# 1-Schematic_rdb_ruler.net
KiCad netlist of a schematic drawn in EasyEDA
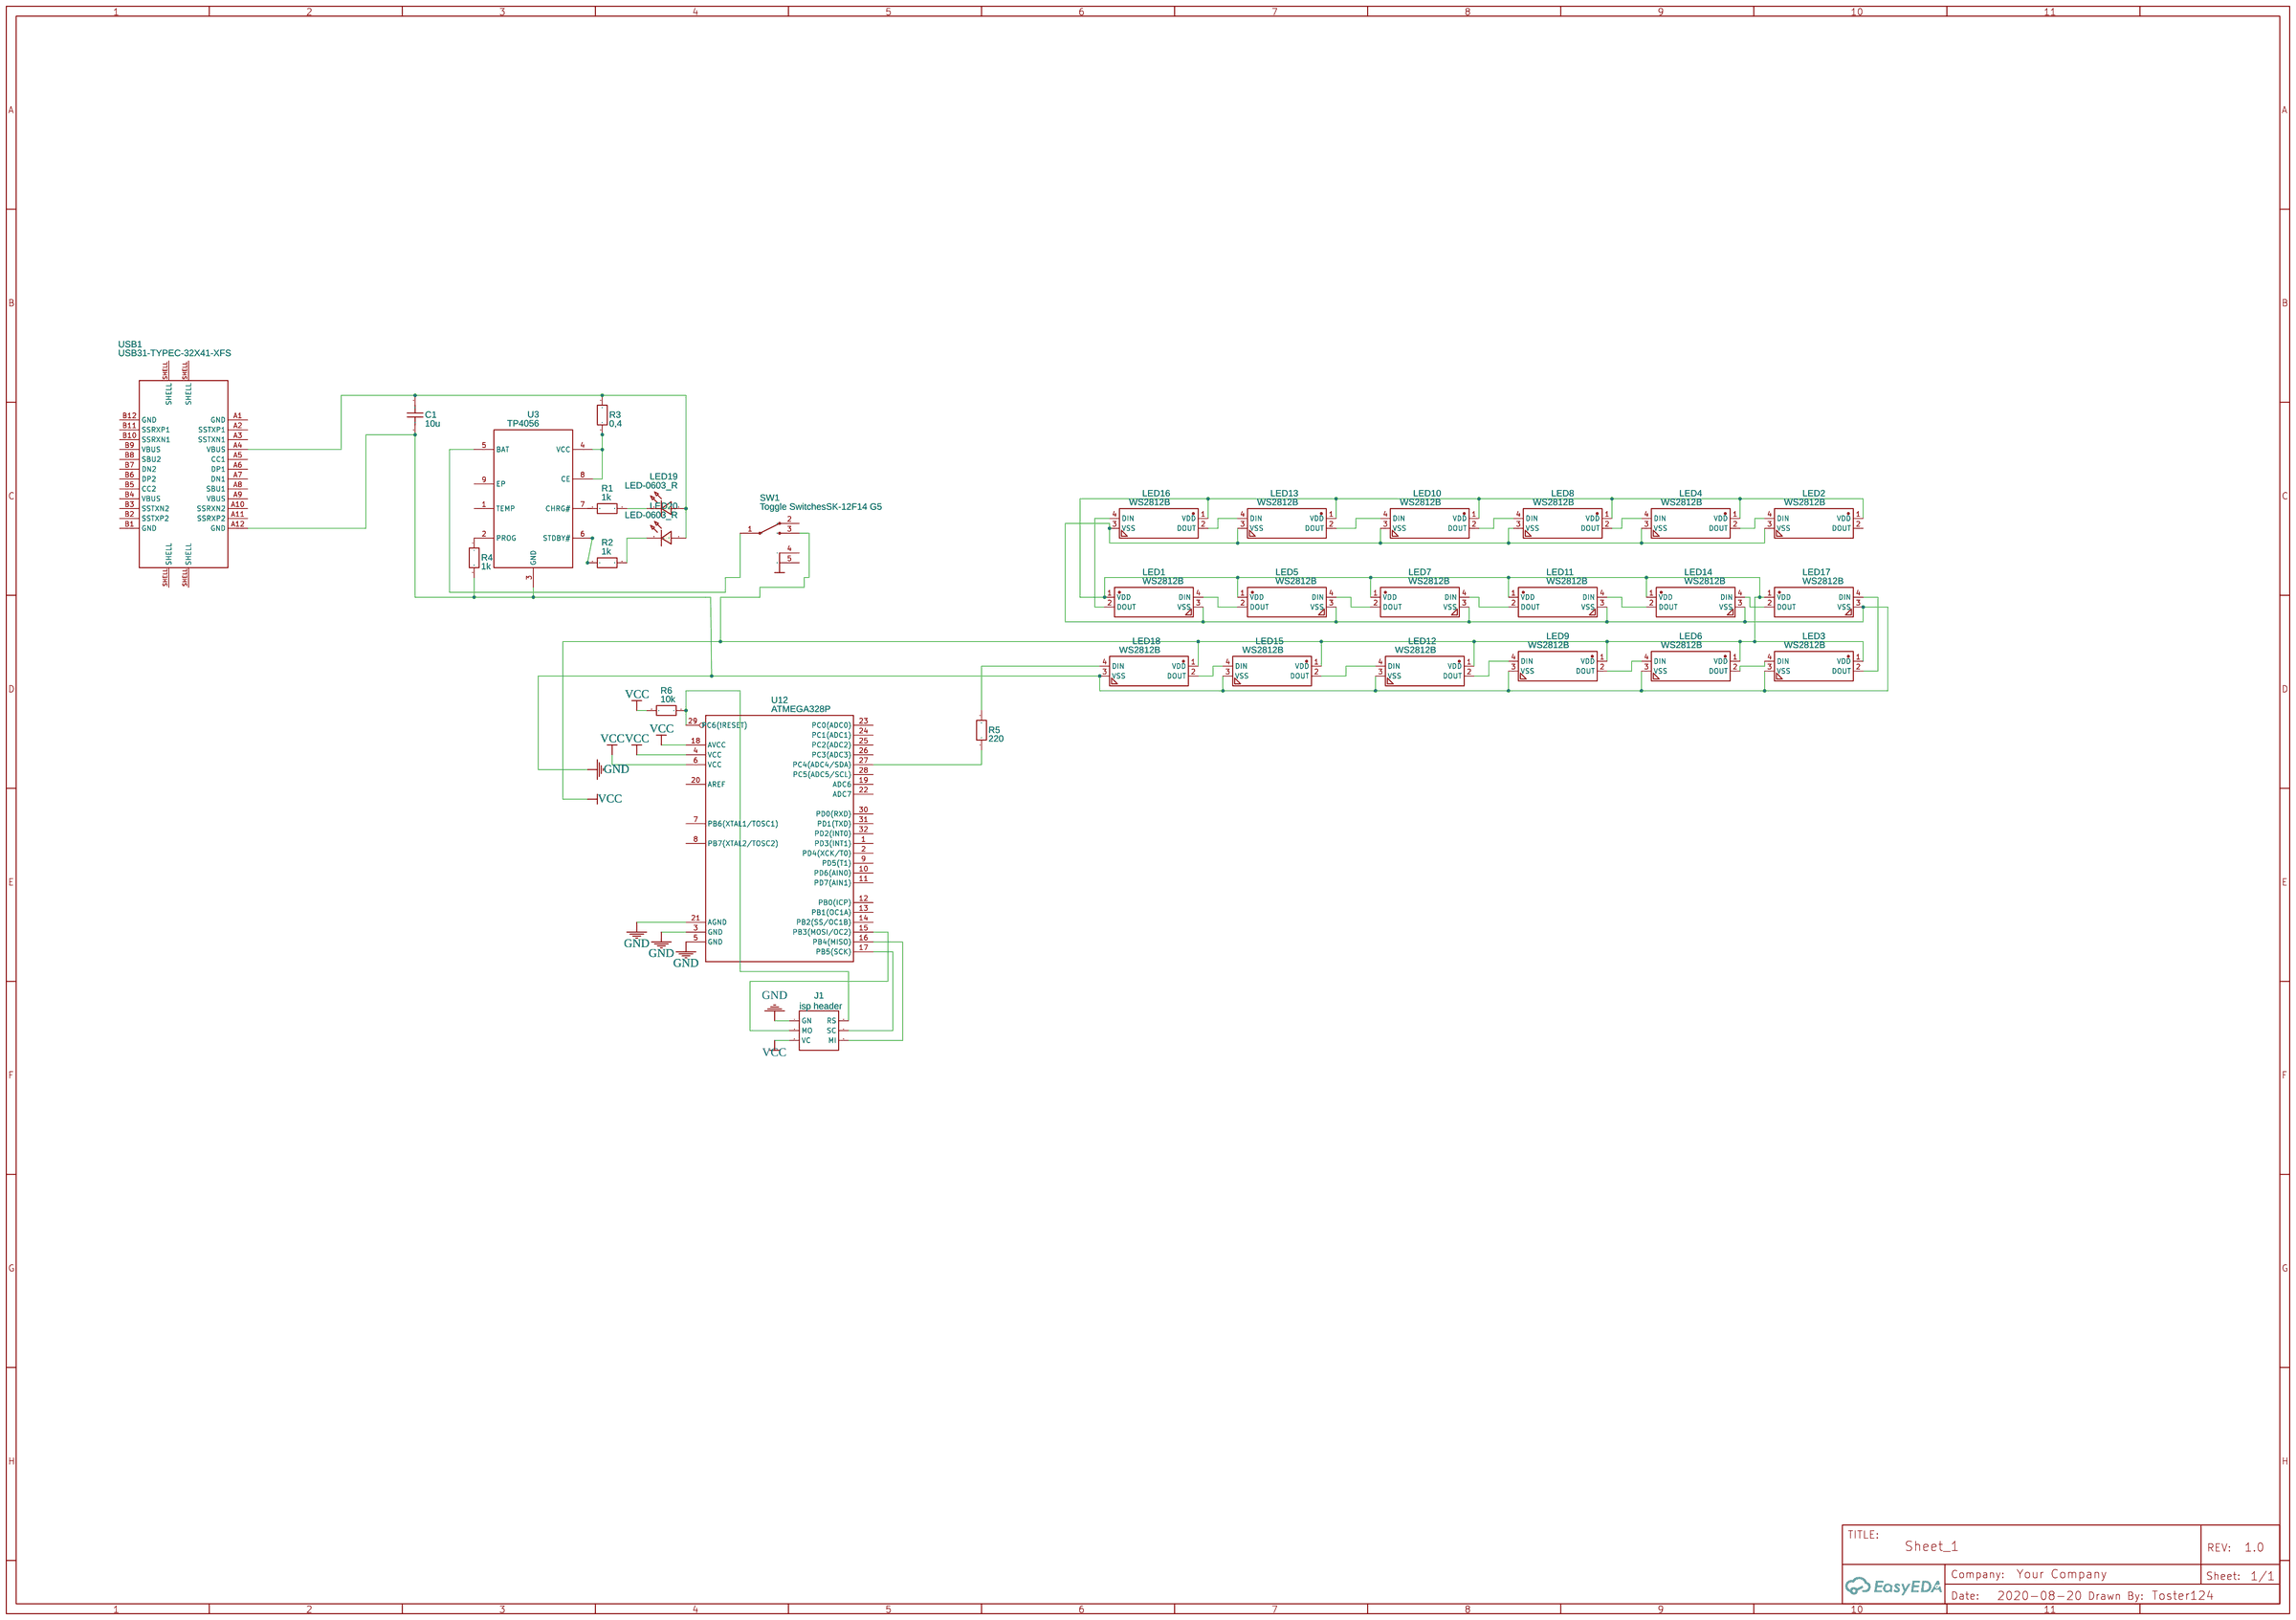
[diagram p0: schematic sheet]

(export (version "E")
  (design (tool "Eeschema 10.0.6"))
  (components
    (comp (ref "C1") (value "10u") (libsource (lib "") (part "C_0603_US")))
    (comp (ref "J1")
      (value "isp header")
      (fields
        (field (name "BOM_Manufacturer Part") "Header-Male-2.54_2x3")
        (field (name "BOM_Supplier Part") "C65114")
      )
      (libsource (lib "") (part "Unknown_1215_-905"))
    )
    (comp (ref "LED1")
      (value "WS2812B")
      (fields (field (name "BOM_Supplier Part") "C114585"))
      (libsource (lib "") (part "WS2812B_1"))
    )
    (comp (ref "LED2")
      (value "WS2812B")
      (fields (field (name "BOM_Supplier Part") "C114585"))
      (libsource (lib "") (part "WS2812B"))
    )
    (comp (ref "LED3")
      (value "WS2812B")
      (fields (field (name "BOM_Supplier Part") "C114585"))
      (libsource (lib "") (part "WS2812B"))
    )
    (comp (ref "LED4")
      (value "WS2812B")
      (fields (field (name "BOM_Supplier Part") "C114585"))
      (libsource (lib "") (part "WS2812B"))
    )
    (comp (ref "LED5")
      (value "WS2812B")
      (fields (field (name "BOM_Supplier Part") "C114585"))
      (libsource (lib "") (part "WS2812B_1"))
    )
    (comp (ref "LED6")
      (value "WS2812B")
      (fields (field (name "BOM_Supplier Part") "C114585"))
      (libsource (lib "") (part "WS2812B"))
    )
    (comp (ref "LED7")
      (value "WS2812B")
      (fields (field (name "BOM_Supplier Part") "C114585"))
      (libsource (lib "") (part "WS2812B_1"))
    )
    (comp (ref "LED8")
      (value "WS2812B")
      (fields (field (name "BOM_Supplier Part") "C114585"))
      (libsource (lib "") (part "WS2812B"))
    )
    (comp (ref "LED9")
      (value "WS2812B")
      (fields (field (name "BOM_Supplier Part") "C114585"))
      (libsource (lib "") (part "WS2812B"))
    )
    (comp (ref "LED10")
      (value "WS2812B")
      (fields (field (name "BOM_Supplier Part") "C114585"))
      (libsource (lib "") (part "WS2812B"))
    )
    (comp (ref "LED11")
      (value "WS2812B")
      (fields (field (name "BOM_Supplier Part") "C114585"))
      (libsource (lib "") (part "WS2812B_1"))
    )
    (comp (ref "LED12")
      (value "WS2812B")
      (fields (field (name "BOM_Supplier Part") "C114585"))
      (libsource (lib "") (part "WS2812B"))
    )
    (comp (ref "LED13")
      (value "WS2812B")
      (fields (field (name "BOM_Supplier Part") "C114585"))
      (libsource (lib "") (part "WS2812B"))
    )
    (comp (ref "LED14")
      (value "WS2812B")
      (fields (field (name "BOM_Supplier Part") "C114585"))
      (libsource (lib "") (part "WS2812B_1"))
    )
    (comp (ref "LED15")
      (value "WS2812B")
      (fields (field (name "BOM_Supplier Part") "C114585"))
      (libsource (lib "") (part "WS2812B"))
    )
    (comp (ref "LED16")
      (value "WS2812B")
      (fields (field (name "BOM_Supplier Part") "C114585"))
      (libsource (lib "") (part "WS2812B"))
    )
    (comp (ref "LED17")
      (value "WS2812B")
      (fields (field (name "BOM_Supplier Part") "C114585"))
      (libsource (lib "") (part "WS2812B_1"))
    )
    (comp (ref "LED18")
      (value "WS2812B")
      (fields (field (name "BOM_Supplier Part") "C114585"))
      (libsource (lib "") (part "WS2812B"))
    )
    (comp (ref "LED19")
      (value "LED-0603_R")
      (fields
        (field (name "BOM_Manufacturer Part") "19-217/R6C-AL1M2VY/3T")
        (field (name "BOM_Supplier Part") "C72044")
      )
      (libsource (lib "") (part "LED-0603_R"))
    )
    (comp (ref "LED20")
      (value "LED-0603_R")
      (fields
        (field (name "BOM_Manufacturer Part") "19-217/R6C-AL1M2VY/3T")
        (field (name "BOM_Supplier Part") "C72044")
      )
      (libsource (lib "") (part "LED-0603_R"))
    )
    (comp (ref "R1") (value "1k") (libsource (lib "") (part "R_0603_EU_2")))
    (comp (ref "R2") (value "1k") (libsource (lib "") (part "R_0603_EU_2")))
    (comp (ref "R3") (value "0,4") (libsource (lib "") (part "R_0603_EU_1")))
    (comp (ref "R4") (value "1k") (libsource (lib "") (part "R_0603_EU_1")))
    (comp (ref "R5") (value "220") (libsource (lib "") (part "R_0603_EU")))
    (comp (ref "R6") (value "10k") (libsource (lib "") (part "R_0603_EU_2")))
    (comp (ref "SW1")
      (value "Toggle SwitchesSK-12F14 G5")
      (fields (field (name "BOM_Supplier Part") "C59902"))
      (libsource (lib "") (part "Toggle SwitchesSK-12F14 G5"))
    )
    (comp (ref "U3")
      (value "TP4056")
      (fields (field (name "BOM_Supplier Part") "C16581"))
      (libsource (lib "") (part "TP4056"))
    )
    (comp (ref "U12") (value "ATMEGA328P") (libsource (lib "") (part "Unknown_1175_-1100")))
    (comp (ref "USB1")
      (value "USB31-TYPEC-32X41-XFS")
      (fields (field (name "BOM_Supplier Part") "C319152"))
      (libsource (lib "") (part "USB31-TYPEC-32X41-XFS"))
    )
  )
  (nets
    (net (code "1") (name "GND") (class "Default")
      (node (ref "C1") (pin "2") (pinfunction "2_2") (pintype "unspecified"))
      (node (ref "J1") (pin "1") (pinfunction "GN_1") (pintype "input"))
      (node (ref "LED1") (pin "3") (pinfunction "VSS_3") (pintype "unspecified"))
      (node (ref "LED10") (pin "3") (pinfunction "VSS_3") (pintype "unspecified"))
      (node (ref "LED11") (pin "3") (pinfunction "VSS_3") (pintype "unspecified"))
      (node (ref "LED12") (pin "3") (pinfunction "VSS_3") (pintype "unspecified"))
      (node (ref "LED13") (pin "3") (pinfunction "VSS_3") (pintype "unspecified"))
      (node (ref "LED14") (pin "3") (pinfunction "VSS_3") (pintype "unspecified"))
      (node (ref "LED15") (pin "3") (pinfunction "VSS_3") (pintype "unspecified"))
      (node (ref "LED16") (pin "3") (pinfunction "VSS_3") (pintype "unspecified"))
      (node (ref "LED17") (pin "3") (pinfunction "VSS_3") (pintype "unspecified"))
      (node (ref "LED18") (pin "3") (pinfunction "VSS_3") (pintype "unspecified"))
      (node (ref "LED2") (pin "3") (pinfunction "VSS_3") (pintype "unspecified"))
      (node (ref "LED3") (pin "3") (pinfunction "VSS_3") (pintype "unspecified"))
      (node (ref "LED4") (pin "3") (pinfunction "VSS_3") (pintype "unspecified"))
      (node (ref "LED5") (pin "3") (pinfunction "VSS_3") (pintype "unspecified"))
      (node (ref "LED6") (pin "3") (pinfunction "VSS_3") (pintype "unspecified"))
      (node (ref "LED7") (pin "3") (pinfunction "VSS_3") (pintype "unspecified"))
      (node (ref "LED8") (pin "3") (pinfunction "VSS_3") (pintype "unspecified"))
      (node (ref "LED9") (pin "3") (pinfunction "VSS_3") (pintype "unspecified"))
      (node (ref "R4") (pin "2") (pinfunction "2_2") (pintype "unspecified"))
      (node (ref "U12") (pin "21") (pinfunction "AGND_21") (pintype "bidirectional"))
      (node (ref "U12") (pin "3") (pinfunction "GND_3") (pintype "bidirectional"))
      (node (ref "U12") (pin "5") (pinfunction "GND_5") (pintype "bidirectional"))
      (node (ref "U3") (pin "3") (pinfunction "GND_3") (pintype "unspecified"))
      (node (ref "USB1") (pin "A12") (pinfunction "GND_A12") (pintype "unspecified"))
    )
    (net (code "2") (name "Net-(C1-Pad1)") (class "Default")
      (node (ref "C1") (pin "1") (pinfunction "1_1") (pintype "unspecified"))
      (node (ref "LED19") (pin "1") (pinfunction "1_1") (pintype "unspecified"))
      (node (ref "LED20") (pin "1") (pinfunction "1_1") (pintype "unspecified"))
      (node (ref "R3") (pin "1") (pinfunction "1_1") (pintype "unspecified"))
      (node (ref "USB1") (pin "A4") (pinfunction "VBUS_A4") (pintype "unspecified"))
    )
    (net (code "3") (name "Net-(J1-MI)") (class "Default")
      (node (ref "J1") (pin "6") (pinfunction "MI_6") (pintype "input"))
      (node (ref "U12") (pin "16") (pinfunction "PB4(MISO)_16") (pintype "bidirectional"))
    )
    (net (code "4") (name "Net-(J1-MO)") (class "Default")
      (node (ref "J1") (pin "3") (pinfunction "MO_3") (pintype "input"))
      (node (ref "U12") (pin "15") (pinfunction "PB3(MOSI/OC2)_15") (pintype "bidirectional"))
    )
    (net (code "5") (name "Net-(J1-RS)") (class "Default")
      (node (ref "J1") (pin "2") (pinfunction "RS_2") (pintype "input"))
      (node (ref "R6") (pin "2") (pinfunction "2_2") (pintype "unspecified"))
      (node (ref "U12") (pin "29") (pinfunction "PC6(!RESET)_29") (pintype "bidirectional"))
    )
    (net (code "6") (name "Net-(J1-SC)") (class "Default")
      (node (ref "J1") (pin "4") (pinfunction "SC_4") (pintype "input"))
      (node (ref "U12") (pin "17") (pinfunction "PB5(SCK)_17") (pintype "bidirectional"))
    )
    (net (code "7") (name "Net-(LED1-DIN)") (class "Default")
      (node (ref "LED1") (pin "4") (pinfunction "DIN_4") (pintype "unspecified"))
      (node (ref "LED5") (pin "2") (pinfunction "DOUT_2") (pintype "unspecified"))
    )
    (net (code "8") (name "Net-(LED1-DOUT)") (class "Default")
      (node (ref "LED1") (pin "2") (pinfunction "DOUT_2") (pintype "unspecified"))
      (node (ref "LED16") (pin "4") (pinfunction "DIN_4") (pintype "unspecified"))
    )
    (net (code "9") (name "Net-(LED2-DIN)") (class "Default")
      (node (ref "LED2") (pin "4") (pinfunction "DIN_4") (pintype "unspecified"))
      (node (ref "LED4") (pin "2") (pinfunction "DOUT_2") (pintype "unspecified"))
    )
    (net (code "10") (name "Net-(LED3-DIN)") (class "Default")
      (node (ref "LED3") (pin "4") (pinfunction "DIN_4") (pintype "unspecified"))
      (node (ref "LED6") (pin "2") (pinfunction "DOUT_2") (pintype "unspecified"))
    )
    (net (code "11") (name "Net-(LED4-DIN)") (class "Default")
      (node (ref "LED4") (pin "4") (pinfunction "DIN_4") (pintype "unspecified"))
      (node (ref "LED8") (pin "2") (pinfunction "DOUT_2") (pintype "unspecified"))
    )
    (net (code "12") (name "Net-(LED5-DIN)") (class "Default")
      (node (ref "LED5") (pin "4") (pinfunction "DIN_4") (pintype "unspecified"))
      (node (ref "LED7") (pin "2") (pinfunction "DOUT_2") (pintype "unspecified"))
    )
    (net (code "13") (name "Net-(LED6-DIN)") (class "Default")
      (node (ref "LED6") (pin "4") (pinfunction "DIN_4") (pintype "unspecified"))
      (node (ref "LED9") (pin "2") (pinfunction "DOUT_2") (pintype "unspecified"))
    )
    (net (code "14") (name "Net-(LED10-DIN)") (class "Default")
      (node (ref "LED10") (pin "4") (pinfunction "DIN_4") (pintype "unspecified"))
      (node (ref "LED13") (pin "2") (pinfunction "DOUT_2") (pintype "unspecified"))
    )
    (net (code "15") (name "Net-(LED10-DOUT)") (class "Default")
      (node (ref "LED10") (pin "2") (pinfunction "DOUT_2") (pintype "unspecified"))
      (node (ref "LED8") (pin "4") (pinfunction "DIN_4") (pintype "unspecified"))
    )
    (net (code "16") (name "Net-(LED11-DIN)") (class "Default")
      (node (ref "LED11") (pin "4") (pinfunction "DIN_4") (pintype "unspecified"))
      (node (ref "LED14") (pin "2") (pinfunction "DOUT_2") (pintype "unspecified"))
    )
    (net (code "17") (name "Net-(LED11-DOUT)") (class "Default")
      (node (ref "LED11") (pin "2") (pinfunction "DOUT_2") (pintype "unspecified"))
      (node (ref "LED7") (pin "4") (pinfunction "DIN_4") (pintype "unspecified"))
    )
    (net (code "18") (name "Net-(LED12-DIN)") (class "Default")
      (node (ref "LED12") (pin "4") (pinfunction "DIN_4") (pintype "unspecified"))
      (node (ref "LED15") (pin "2") (pinfunction "DOUT_2") (pintype "unspecified"))
    )
    (net (code "19") (name "Net-(LED12-DOUT)") (class "Default")
      (node (ref "LED12") (pin "2") (pinfunction "DOUT_2") (pintype "unspecified"))
      (node (ref "LED9") (pin "4") (pinfunction "DIN_4") (pintype "unspecified"))
    )
    (net (code "20") (name "Net-(LED13-DIN)") (class "Default")
      (node (ref "LED13") (pin "4") (pinfunction "DIN_4") (pintype "unspecified"))
      (node (ref "LED16") (pin "2") (pinfunction "DOUT_2") (pintype "unspecified"))
    )
    (net (code "21") (name "Net-(LED14-DIN)") (class "Default")
      (node (ref "LED14") (pin "4") (pinfunction "DIN_4") (pintype "unspecified"))
      (node (ref "LED17") (pin "2") (pinfunction "DOUT_2") (pintype "unspecified"))
    )
    (net (code "22") (name "Net-(LED15-DIN)") (class "Default")
      (node (ref "LED15") (pin "4") (pinfunction "DIN_4") (pintype "unspecified"))
      (node (ref "LED18") (pin "2") (pinfunction "DOUT_2") (pintype "unspecified"))
    )
    (net (code "23") (name "Net-(LED17-DIN)") (class "Default")
      (node (ref "LED17") (pin "4") (pinfunction "DIN_4") (pintype "unspecified"))
      (node (ref "LED3") (pin "2") (pinfunction "DOUT_2") (pintype "unspecified"))
    )
    (net (code "24") (name "Net-(LED18-DIN)") (class "Default")
      (node (ref "LED18") (pin "4") (pinfunction "DIN_4") (pintype "unspecified"))
      (node (ref "R5") (pin "2") (pinfunction "2_2") (pintype "unspecified"))
    )
    (net (code "25") (name "Net-(LED19-Pad2)") (class "Default")
      (node (ref "LED19") (pin "2") (pinfunction "2_2") (pintype "unspecified"))
      (node (ref "R1") (pin "2") (pinfunction "2_2") (pintype "unspecified"))
    )
    (net (code "26") (name "Net-(LED20-Pad2)") (class "Default")
      (node (ref "LED20") (pin "2") (pinfunction "2_2") (pintype "unspecified"))
      (node (ref "R2") (pin "2") (pinfunction "2_2") (pintype "unspecified"))
    )
    (net (code "27") (name "Net-(U3-BAT)") (class "Default")
      (node (ref "SW1") (pin "1") (pinfunction "1_1") (pintype "unspecified"))
      (node (ref "U3") (pin "5") (pinfunction "BAT_5") (pintype "unspecified"))
    )
    (net (code "28") (name "Net-(U3-CE)") (class "Default")
      (node (ref "R3") (pin "2") (pinfunction "2_2") (pintype "unspecified"))
      (node (ref "U3") (pin "4") (pinfunction "VCC_4") (pintype "unspecified"))
      (node (ref "U3") (pin "8") (pinfunction "CE_8") (pintype "unspecified"))
    )
    (net (code "29") (name "Net-(U3-PROG)") (class "Default")
      (node (ref "R4") (pin "1") (pinfunction "1_1") (pintype "unspecified"))
      (node (ref "U3") (pin "2") (pinfunction "PROG_2") (pintype "unspecified"))
    )
    (net (code "30") (name "Net-(U3-STDBY#)") (class "Default")
      (node (ref "R2") (pin "1") (pinfunction "1_1") (pintype "unspecified"))
      (node (ref "U3") (pin "6") (pinfunction "STDBY#_6") (pintype "unspecified"))
    )
    (net (code "31") (name "Net-(U12-PC4(ADC4{slash}SDA))") (class "Default")
      (node (ref "R5") (pin "1") (pinfunction "1_1") (pintype "unspecified"))
      (node (ref "U12") (pin "27") (pinfunction "PC4(ADC4/SDA)_27") (pintype "bidirectional"))
    )
    (net (code "32") (name "VCC") (class "Default")
      (node (ref "J1") (pin "5") (pinfunction "VC_5") (pintype "input"))
      (node (ref "LED1") (pin "1") (pinfunction "VDD_1") (pintype "unspecified"))
      (node (ref "LED10") (pin "1") (pinfunction "VDD_1") (pintype "unspecified"))
      (node (ref "LED11") (pin "1") (pinfunction "VDD_1") (pintype "unspecified"))
      (node (ref "LED12") (pin "1") (pinfunction "VDD_1") (pintype "unspecified"))
      (node (ref "LED13") (pin "1") (pinfunction "VDD_1") (pintype "unspecified"))
      (node (ref "LED14") (pin "1") (pinfunction "VDD_1") (pintype "unspecified"))
      (node (ref "LED15") (pin "1") (pinfunction "VDD_1") (pintype "unspecified"))
      (node (ref "LED16") (pin "1") (pinfunction "VDD_1") (pintype "unspecified"))
      (node (ref "LED17") (pin "1") (pinfunction "VDD_1") (pintype "unspecified"))
      (node (ref "LED18") (pin "1") (pinfunction "VDD_1") (pintype "unspecified"))
      (node (ref "LED2") (pin "1") (pinfunction "VDD_1") (pintype "unspecified"))
      (node (ref "LED3") (pin "1") (pinfunction "VDD_1") (pintype "unspecified"))
      (node (ref "LED4") (pin "1") (pinfunction "VDD_1") (pintype "unspecified"))
      (node (ref "LED5") (pin "1") (pinfunction "VDD_1") (pintype "unspecified"))
      (node (ref "LED6") (pin "1") (pinfunction "VDD_1") (pintype "unspecified"))
      (node (ref "LED7") (pin "1") (pinfunction "VDD_1") (pintype "unspecified"))
      (node (ref "LED8") (pin "1") (pinfunction "VDD_1") (pintype "unspecified"))
      (node (ref "LED9") (pin "1") (pinfunction "VDD_1") (pintype "unspecified"))
      (node (ref "R6") (pin "1") (pinfunction "1_1") (pintype "unspecified"))
      (node (ref "SW1") (pin "3") (pinfunction "3_3") (pintype "unspecified"))
      (node (ref "U12") (pin "18") (pinfunction "AVCC_18") (pintype "bidirectional"))
      (node (ref "U12") (pin "4") (pinfunction "VCC_4") (pintype "bidirectional"))
      (node (ref "U12") (pin "6") (pinfunction "VCC_6") (pintype "bidirectional"))
    )
    (net (code "33") (name "unconnected-(LED2-DOUT-Pad2)") (class "Default")
      (node (ref "LED2") (pin "2") (pinfunction "DOUT_2") (pintype "unspecified"))
    )
    (net (code "34") (name "unconnected-(R1-Pad1)") (class "Default")
      (node (ref "R1") (pin "1") (pinfunction "1_1") (pintype "unspecified"))
    )
    (net (code "35") (name "unconnected-(SW1-Pad2)") (class "Default")
      (node (ref "SW1") (pin "2") (pinfunction "2_2") (pintype "unspecified"))
    )
    (net (code "36") (name "unconnected-(SW1-Pad4)") (class "Default")
      (node (ref "SW1") (pin "4") (pinfunction "4_4") (pintype "unspecified"))
    )
    (net (code "37") (name "unconnected-(SW1-Pad5)") (class "Default")
      (node (ref "SW1") (pin "5") (pinfunction "5_5") (pintype "unspecified"))
    )
    (net (code "38") (name "unconnected-(U3-CHRG#-Pad7)") (class "Default")
      (node (ref "U3") (pin "7") (pinfunction "CHRG#_7") (pintype "unspecified"))
    )
    (net (code "39") (name "unconnected-(U3-EP-Pad9)") (class "Default")
      (node (ref "U3") (pin "9") (pinfunction "EP_9") (pintype "unspecified"))
    )
    (net (code "40") (name "unconnected-(U3-TEMP-Pad1)") (class "Default")
      (node (ref "U3") (pin "1") (pinfunction "TEMP_1") (pintype "unspecified"))
    )
    (net (code "41") (name "unconnected-(U12-ADC6-Pad19)") (class "Default")
      (node (ref "U12") (pin "19") (pinfunction "ADC6_19") (pintype "bidirectional"))
    )
    (net (code "42") (name "unconnected-(U12-ADC7-Pad22)") (class "Default")
      (node (ref "U12") (pin "22") (pinfunction "ADC7_22") (pintype "bidirectional"))
    )
    (net (code "43") (name "unconnected-(U12-AREF-Pad20)") (class "Default")
      (node (ref "U12") (pin "20") (pinfunction "AREF_20") (pintype "bidirectional"))
    )
    (net (code "44") (name "unconnected-(U12-PB0(ICP)-Pad12)") (class "Default")
      (node (ref "U12") (pin "12") (pinfunction "PB0(ICP)_12") (pintype "bidirectional"))
    )
    (net (code "45") (name "unconnected-(U12-PB1(OC1A)-Pad13)") (class "Default")
      (node (ref "U12") (pin "13") (pinfunction "PB1(OC1A)_13") (pintype "bidirectional"))
    )
    (net (code "46") (name "unconnected-(U12-PB2(SS{slash}OC1B)-Pad14)") (class "Default")
      (node (ref "U12") (pin "14") (pinfunction "PB2(SS/OC1B)_14") (pintype "bidirectional"))
    )
    (net (code "47") (name "unconnected-(U12-PB6(XTAL1{slash}TOSC1)-Pad7)") (class "Default")
      (node (ref "U12") (pin "7") (pinfunction "PB6(XTAL1/TOSC1)_7") (pintype "bidirectional"))
    )
    (net (code "48") (name "unconnected-(U12-PB7(XTAL2{slash}TOSC2)-Pad8)") (class "Default")
      (node (ref "U12") (pin "8") (pinfunction "PB7(XTAL2/TOSC2)_8") (pintype "bidirectional"))
    )
    (net (code "49") (name "unconnected-(U12-PC0(ADC0)-Pad23)") (class "Default")
      (node (ref "U12") (pin "23") (pinfunction "PC0(ADC0)_23") (pintype "bidirectional"))
    )
    (net (code "50") (name "unconnected-(U12-PC1(ADC1)-Pad24)") (class "Default")
      (node (ref "U12") (pin "24") (pinfunction "PC1(ADC1)_24") (pintype "bidirectional"))
    )
    (net (code "51") (name "unconnected-(U12-PC2(ADC2)-Pad25)") (class "Default")
      (node (ref "U12") (pin "25") (pinfunction "PC2(ADC2)_25") (pintype "bidirectional"))
    )
    (net (code "52") (name "unconnected-(U12-PC3(ADC3)-Pad26)") (class "Default")
      (node (ref "U12") (pin "26") (pinfunction "PC3(ADC3)_26") (pintype "bidirectional"))
    )
    (net (code "53") (name "unconnected-(U12-PC5(ADC5{slash}SCL)-Pad28)") (class "Default")
      (node (ref "U12") (pin "28") (pinfunction "PC5(ADC5/SCL)_28") (pintype "bidirectional"))
    )
    (net (code "54") (name "unconnected-(U12-PD0(RXD)-Pad30)") (class "Default")
      (node (ref "U12") (pin "30") (pinfunction "PD0(RXD)_30") (pintype "bidirectional"))
    )
    (net (code "55") (name "unconnected-(U12-PD1(TXD)-Pad31)") (class "Default")
      (node (ref "U12") (pin "31") (pinfunction "PD1(TXD)_31") (pintype "bidirectional"))
    )
    (net (code "56") (name "unconnected-(U12-PD2(INT0)-Pad32)") (class "Default")
      (node (ref "U12") (pin "32") (pinfunction "PD2(INT0)_32") (pintype "bidirectional"))
    )
    (net (code "57") (name "unconnected-(U12-PD3(INT1)-Pad1)") (class "Default")
      (node (ref "U12") (pin "1") (pinfunction "PD3(INT1)_1") (pintype "bidirectional"))
    )
    (net (code "58") (name "unconnected-(U12-PD4(XCK{slash}T0)-Pad2)") (class "Default")
      (node (ref "U12") (pin "2") (pinfunction "PD4(XCK/T0)_2") (pintype "bidirectional"))
    )
    (net (code "59") (name "unconnected-(U12-PD5(T1)-Pad9)") (class "Default")
      (node (ref "U12") (pin "9") (pinfunction "PD5(T1)_9") (pintype "bidirectional"))
    )
    (net (code "60") (name "unconnected-(U12-PD6(AIN0)-Pad10)") (class "Default")
      (node (ref "U12") (pin "10") (pinfunction "PD6(AIN0)_10") (pintype "bidirectional"))
    )
    (net (code "61") (name "unconnected-(U12-PD7(AIN1)-Pad11)") (class "Default")
      (node (ref "U12") (pin "11") (pinfunction "PD7(AIN1)_11") (pintype "bidirectional"))
    )
    (net (code "62") (name "unconnected-(USB1-CC1-PadA5)") (class "Default")
      (node (ref "USB1") (pin "A5") (pinfunction "CC1_A5") (pintype "unspecified"))
    )
    (net (code "63") (name "unconnected-(USB1-CC2-PadB5)") (class "Default")
      (node (ref "USB1") (pin "B5") (pinfunction "CC2_B5") (pintype "unspecified"))
    )
    (net (code "64") (name "unconnected-(USB1-DN1-PadA7)") (class "Default")
      (node (ref "USB1") (pin "A7") (pinfunction "DN1_A7") (pintype "unspecified"))
    )
    (net (code "65") (name "unconnected-(USB1-DN2-PadB7)") (class "Default")
      (node (ref "USB1") (pin "B7") (pinfunction "DN2_B7") (pintype "unspecified"))
    )
    (net (code "66") (name "unconnected-(USB1-DP1-PadA6)") (class "Default")
      (node (ref "USB1") (pin "A6") (pinfunction "DP1_A6") (pintype "unspecified"))
    )
    (net (code "67") (name "unconnected-(USB1-DP2-PadB6)") (class "Default")
      (node (ref "USB1") (pin "B6") (pinfunction "DP2_B6") (pintype "unspecified"))
    )
    (net (code "68") (name "unconnected-(USB1-GND-PadA1)") (class "Default")
      (node (ref "USB1") (pin "A1") (pinfunction "GND_A1") (pintype "unspecified"))
    )
    (net (code "69") (name "unconnected-(USB1-GND-PadB1)") (class "Default")
      (node (ref "USB1") (pin "B1") (pinfunction "GND_B1") (pintype "unspecified"))
    )
    (net (code "70") (name "unconnected-(USB1-GND-PadB12)") (class "Default")
      (node (ref "USB1") (pin "B12") (pinfunction "GND_B12") (pintype "unspecified"))
    )
    (net (code "71") (name "unconnected-(USB1-PadSHELL)") (class "Default")
      (node (ref "USB1") (pin "SHELL") (pinfunction "SHELL_SHELL") (pintype "unspecified"))
    )
    (net (code "72") (name "unconnected-(USB1-PadSHELL)_1") (class "Default")
      (node (ref "USB1") (pin "SHELL") (pinfunction "SHELL_SHELL") (pintype "unspecified"))
    )
    (net (code "73") (name "unconnected-(USB1-PadSHELL)_2") (class "Default")
      (node (ref "USB1") (pin "SHELL") (pinfunction "SHELL_SHELL") (pintype "unspecified"))
    )
    (net (code "74") (name "unconnected-(USB1-PadSHELL)_3") (class "Default")
      (node (ref "USB1") (pin "SHELL") (pinfunction "SHELL_SHELL") (pintype "unspecified"))
    )
    (net (code "75") (name "unconnected-(USB1-SBU1-PadA8)") (class "Default")
      (node (ref "USB1") (pin "A8") (pinfunction "SBU1_A8") (pintype "unspecified"))
    )
    (net (code "76") (name "unconnected-(USB1-SBU2-PadB8)") (class "Default")
      (node (ref "USB1") (pin "B8") (pinfunction "SBU2_B8") (pintype "unspecified"))
    )
    (net (code "77") (name "unconnected-(USB1-SSRXN1-PadB10)") (class "Default")
      (node (ref "USB1") (pin "B10") (pinfunction "SSRXN1_B10") (pintype "unspecified"))
    )
    (net (code "78") (name "unconnected-(USB1-SSRXN2-PadA10)") (class "Default")
      (node (ref "USB1") (pin "A10") (pinfunction "SSRXN2_A10") (pintype "unspecified"))
    )
    (net (code "79") (name "unconnected-(USB1-SSRXP1-PadB11)") (class "Default")
      (node (ref "USB1") (pin "B11") (pinfunction "SSRXP1_B11") (pintype "unspecified"))
    )
    (net (code "80") (name "unconnected-(USB1-SSRXP2-PadA11)") (class "Default")
      (node (ref "USB1") (pin "A11") (pinfunction "SSRXP2_A11") (pintype "unspecified"))
    )
    (net (code "81") (name "unconnected-(USB1-SSTXN1-PadA3)") (class "Default")
      (node (ref "USB1") (pin "A3") (pinfunction "SSTXN1_A3") (pintype "unspecified"))
    )
    (net (code "82") (name "unconnected-(USB1-SSTXN2-PadB3)") (class "Default")
      (node (ref "USB1") (pin "B3") (pinfunction "SSTXN2_B3") (pintype "unspecified"))
    )
    (net (code "83") (name "unconnected-(USB1-SSTXP1-PadA2)") (class "Default")
      (node (ref "USB1") (pin "A2") (pinfunction "SSTXP1_A2") (pintype "unspecified"))
    )
    (net (code "84") (name "unconnected-(USB1-SSTXP2-PadB2)") (class "Default")
      (node (ref "USB1") (pin "B2") (pinfunction "SSTXP2_B2") (pintype "unspecified"))
    )
    (net (code "85") (name "unconnected-(USB1-VBUS-PadA9)") (class "Default")
      (node (ref "USB1") (pin "A9") (pinfunction "VBUS_A9") (pintype "unspecified"))
    )
    (net (code "86") (name "unconnected-(USB1-VBUS-PadB4)") (class "Default")
      (node (ref "USB1") (pin "B4") (pinfunction "VBUS_B4") (pintype "unspecified"))
    )
    (net (code "87") (name "unconnected-(USB1-VBUS-PadB9)") (class "Default")
      (node (ref "USB1") (pin "B9") (pinfunction "VBUS_B9") (pintype "unspecified"))
    )
  )
)
